# Motor-Y.net
KiCad netlist of a schematic drawn in Altium Designer
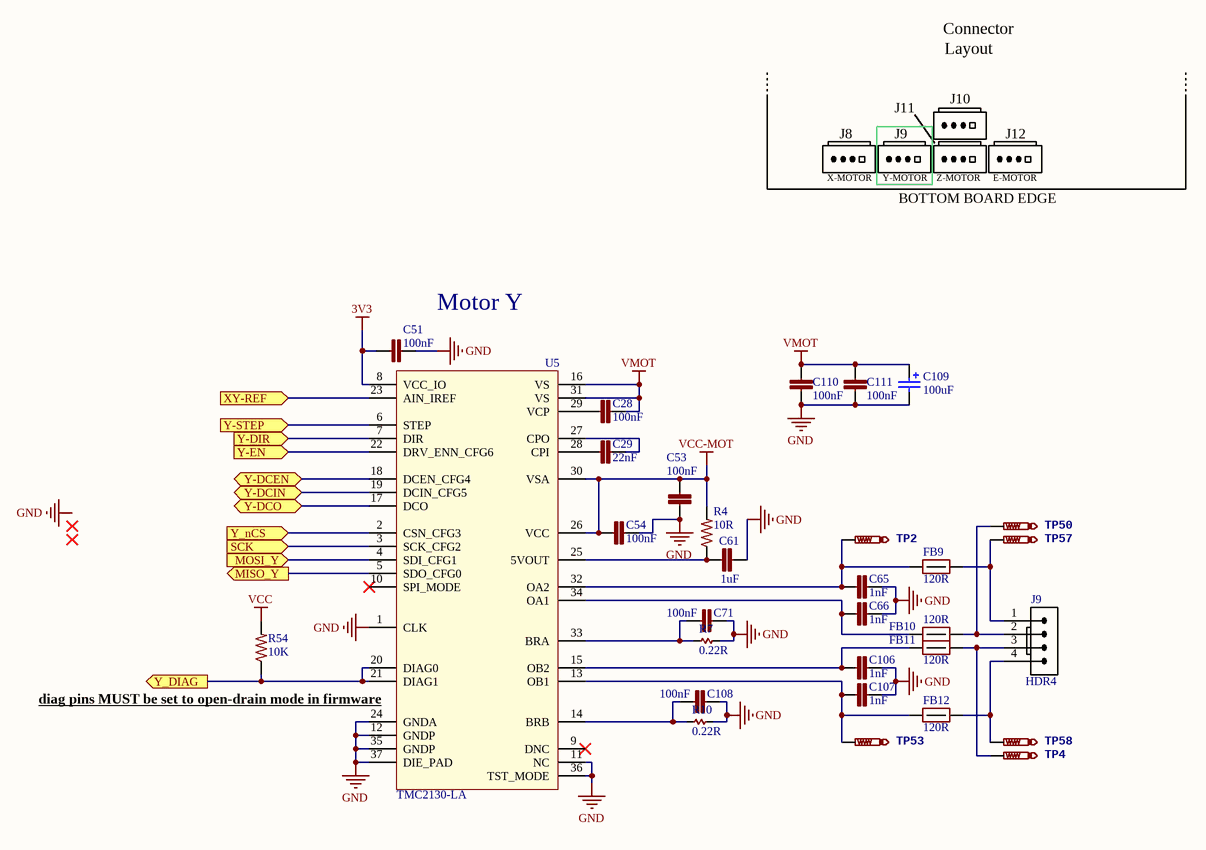
[diagram p0: Motor-Y.SchDoc]

(export (version "E")
  (design (tool "Eeschema 10.0.6"))
  (components
    (comp (ref "C28")
      (value "100nF")
      (footprint "C0603")
      (description "CAP CER 0603 100nF 50V 10% X7R")
      (fields (field (name "MANUFACTURER") "Kemet") (field (name "TOLERANCE") "+/- 10%"))
      (libsource (lib "") (part "C0603C104K5RACTU_2"))
    )
    (comp (ref "C29")
      (value "22nF")
      (footprint "C0402")
      (description "CAP CER 0402 22nF ±10% 50V X7R")
      (fields (field (name "MANUFACTURER") "YAGEO") (field (name "TOLERANCE") "+/- 10%"))
      (libsource (lib "3Delight") (part "GCM155R71H223KA55D"))
    )
    (comp (ref "C51")
      (value "100nF")
      (footprint "C0402")
      (description "CAP CER 0402 100nF 16V 10% X7R")
      (fields (field (name "MANUFACTURER") "Murata") (field (name "TOLERANCE") "+/- 10%"))
      (libsource (lib "3Delight") (part "GRM155R71C104KA88D"))
    )
    (comp (ref "C53")
      (value "100nF")
      (footprint "C0402")
      (description "CAP CER 0402 100nF 16V 10% X7R")
      (fields (field (name "MANUFACTURER") "Murata") (field (name "TOLERANCE") "+/- 10%"))
      (libsource (lib "") (part "GRM155R71C104KA88D_1"))
    )
    (comp (ref "C54")
      (value "100nF")
      (footprint "C0402")
      (description "CAP CER 0402 100nF 16V 10% X7R")
      (fields (field (name "MANUFACTURER") "Murata") (field (name "TOLERANCE") "+/- 10%"))
      (libsource (lib "3Delight") (part "GRM155R71C104KA88D"))
    )
    (comp (ref "C61")
      (value "1uF")
      (footprint "C0402")
      (description "CAP CER 0402 1uF 6.3V 10% X5R")
      (fields (field (name "MANUFACTURER") "Murata") (field (name "TOLERANCE") "+/- 10%"))
      (libsource (lib "3Delight") (part "GRM155R60J105KE19D"))
    )
    (comp (ref "C65")
      (value "1nF")
      (footprint "C0603")
      (description "CAP CER 0603  1nF 50v 10% X7R")
      (fields (field (name "MANUFACTURER") "Kemet") (field (name "TOLERANCE") "+/- 10%"))
      (libsource (lib "3Delight") (part "C0603C102K5RACTU"))
    )
    (comp (ref "C66")
      (value "1nF")
      (footprint "C0603")
      (description "CAP CER 0603  1nF 50v 10% X7R")
      (fields (field (name "MANUFACTURER") "Kemet") (field (name "TOLERANCE") "+/- 10%"))
      (libsource (lib "3Delight") (part "C0603C102K5RACTU"))
    )
    (comp (ref "C71")
      (value "100nF")
      (footprint "C0603")
      (description "CAP CER 0603 100nF 50V 10% X7R")
      (fields (field (name "MANUFACTURER") "Kemet") (field (name "TOLERANCE") "+/- 10%"))
      (libsource (lib "") (part "C0603C104K5RACTU_1"))
    )
    (comp (ref "C106")
      (value "1nF")
      (footprint "C0603")
      (description "CAP CER 0603  1nF 50v 10% X7R")
      (fields (field (name "MANUFACTURER") "Kemet") (field (name "TOLERANCE") "+/- 10%"))
      (libsource (lib "3Delight") (part "C0603C102K5RACTU"))
    )
    (comp (ref "C107")
      (value "1nF")
      (footprint "C0603")
      (description "CAP CER 0603  1nF 50v 10% X7R")
      (fields (field (name "MANUFACTURER") "Kemet") (field (name "TOLERANCE") "+/- 10%"))
      (libsource (lib "3Delight") (part "C0603C102K5RACTU"))
    )
    (comp (ref "C108")
      (value "100nF")
      (footprint "C0603")
      (description "CAP CER 0603 100nF 50V 10% X7R")
      (fields (field (name "MANUFACTURER") "Kemet") (field (name "TOLERANCE") "+/- 10%"))
      (libsource (lib "") (part "C0603C104K5RACTU_1"))
    )
    (comp (ref "C109")
      (value "100uF")
      (footprint "CAP-ELEC-063063077")
      (description "CAP ALUM 100UF 35V 20% SMD")
      (fields (field (name "MANUFACTURER") "Nichicon") (field (name "TOLERANCE") "+/- 20%"))
      (libsource (lib "3Delight") (part "UWT1V101MCL1GS"))
    )
    (comp (ref "C110")
      (value "100nF")
      (footprint "C0603")
      (description "CAP CER 0603 100nF 50V 10% X7R")
      (fields (field (name "MANUFACTURER") "Kemet") (field (name "TOLERANCE") "+/- 10%"))
      (libsource (lib "3Delight") (part "C0603C104K5RACTU"))
    )
    (comp (ref "C111")
      (value "100nF")
      (footprint "C0603")
      (description "CAP CER 0603 100nF 50V 10% X7R")
      (fields (field (name "MANUFACTURER") "Kemet") (field (name "TOLERANCE") "+/- 10%"))
      (libsource (lib "3Delight") (part "C0603C104K5RACTU"))
    )
    (comp (ref "FB9")
      (value "120R")
      (footprint "FB0603")
      (description "FERRITE BEAD 120 OHM 0603 1LN")
      (fields (field (name "MANUFACTURER") "Samsung") (field (name "PART") "FERRITE 120R 3A 0603"))
      (libsource (lib "Inductors") (part "FERRITE 120R 3A 0603"))
    )
    (comp (ref "FB10")
      (value "120R")
      (footprint "FB0603")
      (description "FERRITE BEAD 120 OHM 0603 1LN")
      (fields (field (name "MANUFACTURER") "Samsung") (field (name "PART") "FERRITE 120R 3A 0603"))
      (libsource (lib "Inductors") (part "FERRITE 120R 3A 0603"))
    )
    (comp (ref "FB11")
      (value "120R")
      (footprint "FB0603")
      (description "FERRITE BEAD 120 OHM 0603 1LN")
      (fields (field (name "MANUFACTURER") "Samsung") (field (name "PART") "FERRITE 120R 3A 0603"))
      (libsource (lib "Inductors") (part "FERRITE 120R 3A 0603"))
    )
    (comp (ref "FB12")
      (value "120R")
      (footprint "FB0603")
      (description "FERRITE BEAD 120 OHM 0603 1LN")
      (fields (field (name "MANUFACTURER") "Samsung") (field (name "PART") "FERRITE 120R 3A 0603"))
      (libsource (lib "Inductors") (part "FERRITE 120R 3A 0603"))
    )
    (comp (ref "J9")
      (value "HDR4")
      (footprint "4POL254")
      (description "Molex 4 Pin Clip Connector")
      (fields (field (name "MANUFACTURER") "Molex") (field (name "PART") "4 Pin Conn"))
      (libsource (lib "3Delight") (part "CONN 4PIN 0.1{dblquote} VERT SHRD LOCK ALT"))
    )
    (comp (ref "R4")
      (value "10R")
      (footprint "R0402")
      (description "RES SMD 10 OHM 1% 1/16W 0402")
      (fields (field (name "MANUFACTURER") "Yageo") (field (name "TOLERANCE") "+/- 1%"))
      (libsource (lib "3Delight") (part "RC0402FR-0710RL"))
    )
    (comp (ref "R7")
      (value "0.22R")
      (footprint "R1206")
      (description "RES SMD 0.22 OHM 1% 1/3W 1206")
      (fields (field (name "MANUFACTURER") "Panasonic") (field (name "TOLERANCE") "+/- 1%"))
      (libsource (lib "Resistors") (part "0.22R 1% 1206"))
    )
    (comp (ref "R10")
      (value "0.22R")
      (footprint "R1206")
      (description "RES SMD 0.22 OHM 1% 1/3W 1206")
      (fields (field (name "MANUFACTURER") "Panasonic") (field (name "TOLERANCE") "+/- 1%"))
      (libsource (lib "Resistors") (part "0.22R 1% 1206"))
    )
    (comp (ref "R54")
      (value "10K")
      (footprint "R0402")
      (description "RES SMD 10K OHM 1% 1/16W 0402")
      (fields (field (name "MANUFACTURER") "Yageo") (field (name "PART") "10k 1% 0402"))
      (libsource (lib "3Delight") (part "RC0402FR-0710KP"))
    )
    (comp (ref "TP2")
      (value "TestPoint")
      (footprint "TP1-27")
      (description "Test Point")
      (libsource (lib "3Delight") (part "TestPoint"))
    )
    (comp (ref "TP4")
      (value "TestPoint")
      (footprint "TP1-27")
      (description "Test Point")
      (libsource (lib "3Delight") (part "TestPoint"))
    )
    (comp (ref "TP50")
      (value "TestPoint")
      (footprint "TP1-27")
      (description "Test Point")
      (libsource (lib "3Delight") (part "TestPoint"))
    )
    (comp (ref "TP53")
      (value "TestPoint")
      (footprint "TP1-27")
      (description "Test Point")
      (libsource (lib "3Delight") (part "TestPoint"))
    )
    (comp (ref "TP57")
      (value "TestPoint")
      (footprint "TP1-27")
      (description "Test Point")
      (libsource (lib "3Delight") (part "TestPoint"))
    )
    (comp (ref "TP58")
      (value "TestPoint")
      (footprint "TP1-27")
      (description "Test Point")
      (libsource (lib "3Delight") (part "TestPoint"))
    )
    (comp (ref "U5")
      (value "TMC2130-LA")
      (footprint "QFN36-50P500X600X900_HS-37N")
      (description "IC STEPPER MOTOR DVR SPI 36QFN")
      (fields (field (name "MANUFACTURER") "Trinamic") (field (name "PART") "TMC2130"))
      (libsource (lib "ICs-Motor Controller") (part "TMC2130-LA-T"))
    )
  )
  (nets
    (net (code "1") (name "/MISO_Y") (class "Default")
      (node (ref "U5") (pin "5") (pinfunction "SDO_CFG0_5") (pintype "passive"))
    )
    (net (code "2") (name "/MOSI_Y") (class "Default")
      (node (ref "U5") (pin "4") (pinfunction "SDI_CFG1_4") (pintype "passive"))
    )
    (net (code "3") (name "/SCK") (class "Default")
      (node (ref "U5") (pin "3") (pinfunction "SCK_CFG2_3") (pintype "passive"))
    )
    (net (code "4") (name "/XY-REF") (class "Default")
      (node (ref "U5") (pin "23") (pinfunction "AIN_IREF_23") (pintype "passive"))
    )
    (net (code "5") (name "/Y-DCEN") (class "Default")
      (node (ref "U5") (pin "18") (pinfunction "DCEN_CFG4_18") (pintype "passive"))
    )
    (net (code "6") (name "/Y-DCIN") (class "Default")
      (node (ref "U5") (pin "19") (pinfunction "DCIN_CFG5_19") (pintype "passive"))
    )
    (net (code "7") (name "/Y-DCO") (class "Default")
      (node (ref "U5") (pin "17") (pinfunction "DCO_17") (pintype "passive"))
    )
    (net (code "8") (name "/Y-DIR") (class "Default")
      (node (ref "U5") (pin "7") (pinfunction "DIR_7") (pintype "passive"))
    )
    (net (code "9") (name "/Y-EN") (class "Default")
      (node (ref "U5") (pin "22") (pinfunction "DRV_ENN_CFG6_22") (pintype "passive"))
    )
    (net (code "10") (name "/Y-STEP") (class "Default")
      (node (ref "U5") (pin "6") (pinfunction "STEP_6") (pintype "passive"))
    )
    (net (code "11") (name "/Y_DIAG") (class "Default")
      (node (ref "R54") (pin "1") (pinfunction "1_1") (pintype "passive"))
      (node (ref "U5") (pin "20") (pinfunction "DIAG0_20") (pintype "passive"))
      (node (ref "U5") (pin "21") (pinfunction "DIAG1_21") (pintype "passive"))
    )
    (net (code "12") (name "/Y_nCS") (class "Default")
      (node (ref "U5") (pin "2") (pinfunction "CSN_CFG3_2") (pintype "passive"))
    )
    (net (code "13") (name "3V3") (class "Default")
      (node (ref "C51") (pin "2") (pinfunction "2_2") (pintype "passive"))
      (node (ref "U5") (pin "8") (pinfunction "VCC_IO_8") (pintype "passive"))
    )
    (net (code "14") (name "GND") (class "Default")
      (node (ref "C106") (pin "2") (pinfunction "2_2") (pintype "passive"))
      (node (ref "C107") (pin "2") (pinfunction "2_2") (pintype "passive"))
      (node (ref "C108") (pin "1") (pinfunction "1_1") (pintype "passive"))
      (node (ref "C109") (pin "2") (pinfunction "2_2") (pintype "passive"))
      (node (ref "C110") (pin "1") (pinfunction "1_1") (pintype "passive"))
      (node (ref "C111") (pin "1") (pinfunction "1_1") (pintype "passive"))
      (node (ref "C51") (pin "1") (pinfunction "1_1") (pintype "passive"))
      (node (ref "C53") (pin "1") (pinfunction "1_1") (pintype "passive"))
      (node (ref "C54") (pin "1") (pinfunction "1_1") (pintype "passive"))
      (node (ref "C61") (pin "2") (pinfunction "2_2") (pintype "passive"))
      (node (ref "C65") (pin "2") (pinfunction "2_2") (pintype "passive"))
      (node (ref "C66") (pin "2") (pinfunction "2_2") (pintype "passive"))
      (node (ref "C71") (pin "1") (pinfunction "1_1") (pintype "passive"))
      (node (ref "R10") (pin "2") (pinfunction "2_2") (pintype "passive"))
      (node (ref "R7") (pin "2") (pinfunction "2_2") (pintype "passive"))
      (node (ref "U5") (pin "1") (pinfunction "CLK_1") (pintype "passive"))
      (node (ref "U5") (pin "11") (pinfunction "NC_11") (pintype "passive"))
      (node (ref "U5") (pin "12") (pinfunction "GNDP_12") (pintype "passive"))
      (node (ref "U5") (pin "24") (pinfunction "GNDA_24") (pintype "passive"))
      (node (ref "U5") (pin "35") (pinfunction "GNDP_35") (pintype "passive"))
      (node (ref "U5") (pin "36") (pinfunction "TST_MODE_36") (pintype "passive"))
      (node (ref "U5") (pin "37") (pinfunction "DIE_PAD_37") (pintype "passive"))
    )
    (net (code "15") (name "Net-(FB9-Pad2)") (class "Default")
      (node (ref "FB9") (pin "2") (pinfunction "2_2") (pintype "passive"))
      (node (ref "J9") (pin "1") (pinfunction "1_1") (pintype "passive"))
      (node (ref "TP57") (pin "TP") (pinfunction "TP_TP") (pintype "passive"))
    )
    (net (code "16") (name "Net-(FB10-Pad2)") (class "Default")
      (node (ref "FB10") (pin "2") (pinfunction "2_2") (pintype "passive"))
      (node (ref "J9") (pin "2") (pinfunction "2_2") (pintype "passive"))
      (node (ref "TP50") (pin "TP") (pinfunction "TP_TP") (pintype "passive"))
    )
    (net (code "17") (name "Net-(FB11-Pad2)") (class "Default")
      (node (ref "FB11") (pin "2") (pinfunction "2_2") (pintype "passive"))
      (node (ref "J9") (pin "3") (pinfunction "3_3") (pintype "passive"))
      (node (ref "TP4") (pin "TP") (pinfunction "TP_TP") (pintype "passive"))
    )
    (net (code "18") (name "Net-(FB12-Pad2)") (class "Default")
      (node (ref "FB12") (pin "2") (pinfunction "2_2") (pintype "passive"))
      (node (ref "J9") (pin "4") (pinfunction "4_4") (pintype "passive"))
      (node (ref "TP58") (pin "TP") (pinfunction "TP_TP") (pintype "passive"))
    )
    (net (code "19") (name "Net-(U5-5VOUT)") (class "Default")
      (node (ref "C61") (pin "1") (pinfunction "1_1") (pintype "passive"))
      (node (ref "R4") (pin "1") (pinfunction "1_1") (pintype "passive"))
      (node (ref "U5") (pin "25") (pinfunction "5VOUT_25") (pintype "passive"))
    )
    (net (code "20") (name "Net-(U5-BRA)") (class "Default")
      (node (ref "C71") (pin "2") (pinfunction "2_2") (pintype "passive"))
      (node (ref "R7") (pin "1") (pinfunction "1_1") (pintype "passive"))
      (node (ref "U5") (pin "33") (pinfunction "BRA_33") (pintype "passive"))
    )
    (net (code "21") (name "Net-(U5-BRB)") (class "Default")
      (node (ref "C108") (pin "2") (pinfunction "2_2") (pintype "passive"))
      (node (ref "R10") (pin "1") (pinfunction "1_1") (pintype "passive"))
      (node (ref "U5") (pin "14") (pinfunction "BRB_14") (pintype "passive"))
    )
    (net (code "22") (name "Net-(U5-CPI)") (class "Default")
      (node (ref "C29") (pin "1") (pinfunction "1_1") (pintype "passive"))
      (node (ref "U5") (pin "28") (pinfunction "CPI_28") (pintype "passive"))
    )
    (net (code "23") (name "Net-(U5-CPO)") (class "Default")
      (node (ref "C29") (pin "2") (pinfunction "2_2") (pintype "passive"))
      (node (ref "U5") (pin "27") (pinfunction "CPO_27") (pintype "passive"))
    )
    (net (code "24") (name "Net-(U5-OA1)") (class "Default")
      (node (ref "C66") (pin "1") (pinfunction "1_1") (pintype "passive"))
      (node (ref "FB10") (pin "1") (pinfunction "1_1") (pintype "passive"))
      (node (ref "U5") (pin "34") (pinfunction "OA1_34") (pintype "passive"))
    )
    (net (code "25") (name "Net-(U5-OA2)") (class "Default")
      (node (ref "C65") (pin "1") (pinfunction "1_1") (pintype "passive"))
      (node (ref "FB9") (pin "1") (pinfunction "1_1") (pintype "passive"))
      (node (ref "TP2") (pin "TP") (pinfunction "TP_TP") (pintype "passive"))
      (node (ref "U5") (pin "32") (pinfunction "OA2_32") (pintype "passive"))
    )
    (net (code "26") (name "Net-(U5-OB1)") (class "Default")
      (node (ref "C107") (pin "1") (pinfunction "1_1") (pintype "passive"))
      (node (ref "FB12") (pin "1") (pinfunction "1_1") (pintype "passive"))
      (node (ref "TP53") (pin "TP") (pinfunction "TP_TP") (pintype "passive"))
      (node (ref "U5") (pin "13") (pinfunction "OB1_13") (pintype "passive"))
    )
    (net (code "27") (name "Net-(U5-OB2)") (class "Default")
      (node (ref "C106") (pin "1") (pinfunction "1_1") (pintype "passive"))
      (node (ref "FB11") (pin "1") (pinfunction "1_1") (pintype "passive"))
      (node (ref "U5") (pin "15") (pinfunction "OB2_15") (pintype "passive"))
    )
    (net (code "28") (name "Net-(U5-VCP)") (class "Default")
      (node (ref "C28") (pin "1") (pinfunction "1_1") (pintype "passive"))
      (node (ref "U5") (pin "29") (pinfunction "VCP_29") (pintype "passive"))
    )
    (net (code "29") (name "VCC") (class "Default")
      (node (ref "R54") (pin "2") (pinfunction "2_2") (pintype "passive"))
    )
    (net (code "30") (name "VCC-MOT") (class "Default")
      (node (ref "C53") (pin "2") (pinfunction "2_2") (pintype "passive"))
      (node (ref "C54") (pin "2") (pinfunction "2_2") (pintype "passive"))
      (node (ref "R4") (pin "2") (pinfunction "2_2") (pintype "passive"))
      (node (ref "U5") (pin "26") (pinfunction "VCC_26") (pintype "passive"))
      (node (ref "U5") (pin "30") (pinfunction "VSA_30") (pintype "passive"))
    )
    (net (code "31") (name "VMOT") (class "Default")
      (node (ref "C109") (pin "1") (pinfunction "1_1") (pintype "passive"))
      (node (ref "C110") (pin "2") (pinfunction "2_2") (pintype "passive"))
      (node (ref "C111") (pin "2") (pinfunction "2_2") (pintype "passive"))
      (node (ref "C28") (pin "2") (pinfunction "2_2") (pintype "passive"))
      (node (ref "U5") (pin "16") (pinfunction "VS_16") (pintype "passive"))
      (node (ref "U5") (pin "31") (pinfunction "VS_31") (pintype "passive"))
    )
    (net (code "32") (name "unconnected-(U5-DNC-Pad9)") (class "Default")
      (node (ref "U5") (pin "9") (pinfunction "DNC_9") (pintype "passive+no_connect"))
    )
    (net (code "33") (name "unconnected-(U5-SPI_MODE-Pad10)") (class "Default")
      (node (ref "U5") (pin "10") (pinfunction "SPI_MODE_10") (pintype "passive+no_connect"))
    )
  )
)
